# Raspberry_Pi2_Expansion_Slot.net
KiCad netlist of a schematic drawn in Altium Designer
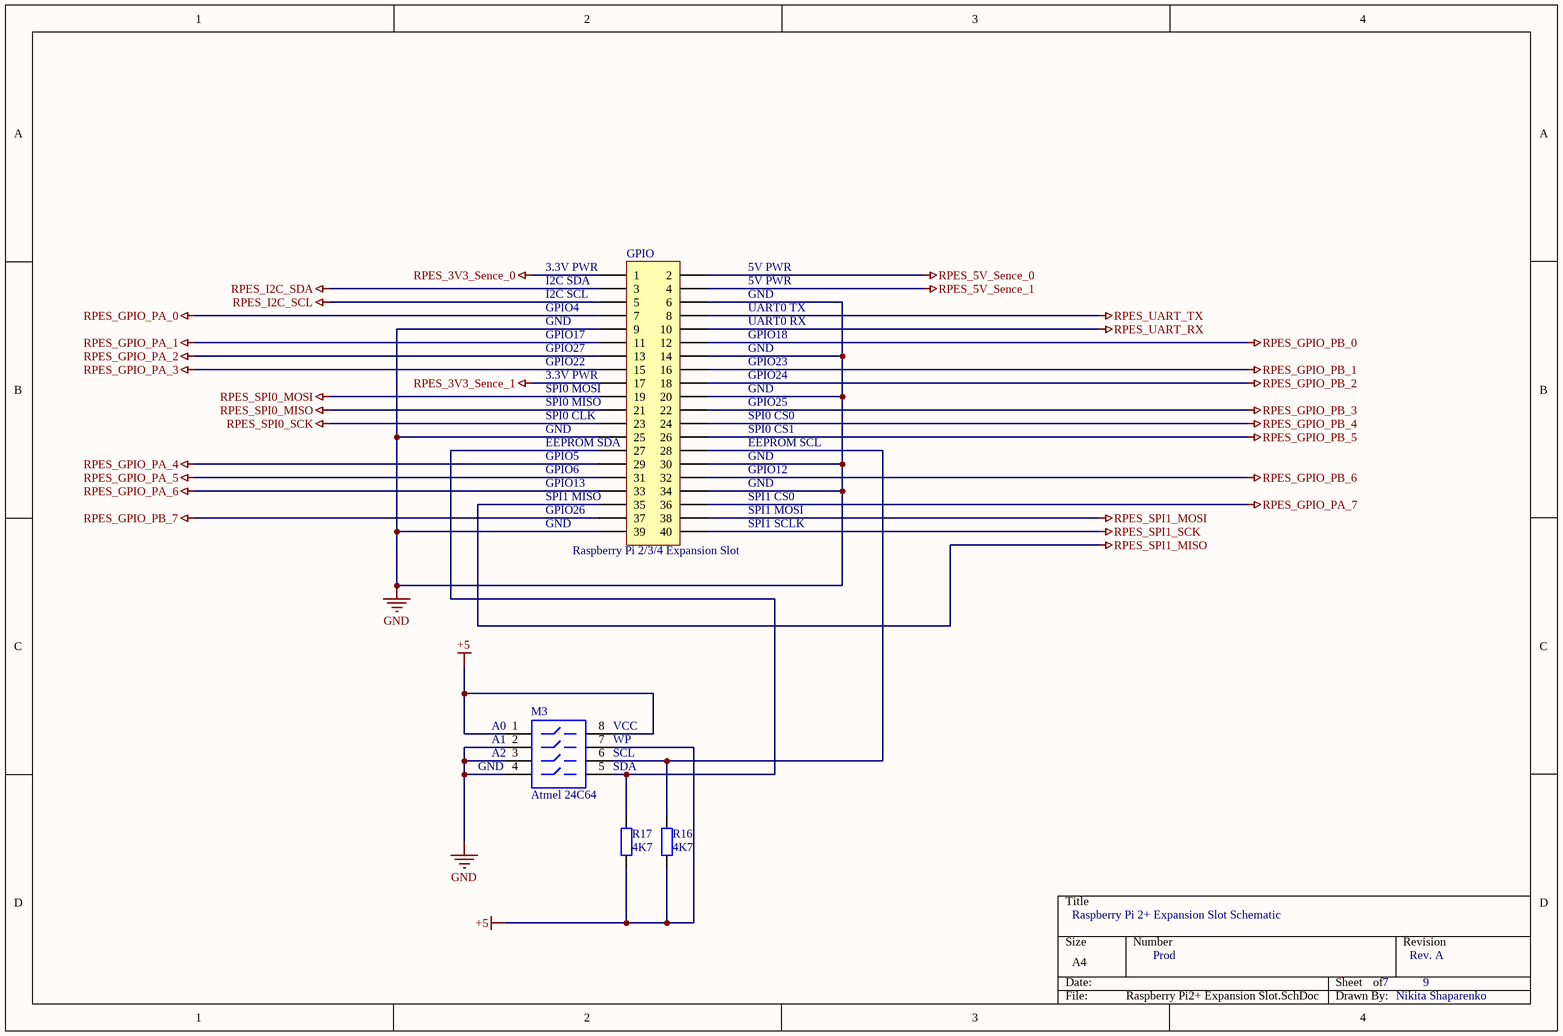
[diagram p0: Raspberry Pi2+ Expansion Slot.SchDoc]

(export (version "E")
  (design (tool "Eeschema 10.0.6"))
  (components
    (comp (ref "GPIO")
      (value "Raspberry Pi 2/3/4 Expansion Slot")
      (footprint "HDR2X20")
      (description "Header, 20-Pin, Dual row")
      (fields (field (name "PUBLISHER") "Altium Limited"))
      (libsource (lib "Miscellaneous Connectors") (part "Header 20X2"))
    )
    (comp (ref "M3")
      (value "Atmel 24C64")
      (footprint "DIP-8")
      (description "DIP Switch")
      (fields (field (name "PUBLISHER") "Altium Limited"))
      (libsource (lib "Miscellaneous Devices") (part "SW-DIP4"))
    )
    (comp (ref "R16")
      (value "4K7")
      (footprint "AXIAL-0.4")
      (description "Resistor")
      (fields (field (name "Comment") "Res2") (field (name "PUBLISHER") "Altium Limited"))
      (libsource (lib "Miscellaneous Devices") (part "Res2"))
    )
    (comp (ref "R17")
      (value "4K7")
      (footprint "AXIAL-0.4")
      (description "Resistor")
      (fields (field (name "Comment") "Res2") (field (name "PUBLISHER") "Altium Limited"))
      (libsource (lib "Miscellaneous Devices") (part "Res2"))
    )
  )
  (nets
    (net (code "1") (name "+5") (class "Default")
      (node (ref "M3") (pin "1") (pinfunction "1_1") (pintype "passive"))
      (node (ref "M3") (pin "7") (pinfunction "7_7") (pintype "passive"))
      (node (ref "M3") (pin "8") (pinfunction "8_8") (pintype "passive"))
      (node (ref "R16") (pin "1") (pinfunction "1_1") (pintype "passive"))
      (node (ref "R17") (pin "1") (pinfunction "1_1") (pintype "passive"))
    )
    (net (code "2") (name "GND") (class "Default")
      (node (ref "GPIO") (pin "14") (pinfunction "14_14") (pintype "passive"))
      (node (ref "GPIO") (pin "20") (pinfunction "20_20") (pintype "passive"))
      (node (ref "GPIO") (pin "25") (pinfunction "25_25") (pintype "passive"))
      (node (ref "GPIO") (pin "30") (pinfunction "30_30") (pintype "passive"))
      (node (ref "GPIO") (pin "34") (pinfunction "34_34") (pintype "passive"))
      (node (ref "GPIO") (pin "39") (pinfunction "39_39") (pintype "passive"))
      (node (ref "GPIO") (pin "6") (pinfunction "6_6") (pintype "passive"))
      (node (ref "GPIO") (pin "9") (pinfunction "9_9") (pintype "passive"))
      (node (ref "M3") (pin "2") (pinfunction "2_2") (pintype "passive"))
      (node (ref "M3") (pin "3") (pinfunction "3_3") (pintype "passive"))
      (node (ref "M3") (pin "4") (pinfunction "4_4") (pintype "passive"))
    )
    (net (code "3") (name "Net-(GPIO-Pad27)") (class "Default")
      (node (ref "GPIO") (pin "27") (pinfunction "27_27") (pintype "passive"))
      (node (ref "M3") (pin "5") (pinfunction "5_5") (pintype "passive"))
      (node (ref "R17") (pin "2") (pinfunction "2_2") (pintype "passive"))
    )
    (net (code "4") (name "Net-(GPIO-Pad28)") (class "Default")
      (node (ref "GPIO") (pin "28") (pinfunction "28_28") (pintype "passive"))
      (node (ref "M3") (pin "6") (pinfunction "6_6") (pintype "passive"))
      (node (ref "R16") (pin "2") (pinfunction "2_2") (pintype "passive"))
    )
    (net (code "5") (name "RPES_3V3_Sence_0") (class "Default")
      (node (ref "GPIO") (pin "1") (pinfunction "1_1") (pintype "passive"))
    )
    (net (code "6") (name "RPES_3V3_Sence_1") (class "Default")
      (node (ref "GPIO") (pin "17") (pinfunction "17_17") (pintype "passive"))
    )
    (net (code "7") (name "RPES_5V_Sence_0") (class "Default")
      (node (ref "GPIO") (pin "2") (pinfunction "2_2") (pintype "passive"))
    )
    (net (code "8") (name "RPES_5V_Sence_1") (class "Default")
      (node (ref "GPIO") (pin "4") (pinfunction "4_4") (pintype "passive"))
    )
    (net (code "9") (name "RPES_GPIO_PA_0") (class "Default")
      (node (ref "GPIO") (pin "7") (pinfunction "7_7") (pintype "passive"))
    )
    (net (code "10") (name "RPES_GPIO_PA_1") (class "Default")
      (node (ref "GPIO") (pin "11") (pinfunction "11_11") (pintype "passive"))
    )
    (net (code "11") (name "RPES_GPIO_PA_2") (class "Default")
      (node (ref "GPIO") (pin "13") (pinfunction "13_13") (pintype "passive"))
    )
    (net (code "12") (name "RPES_GPIO_PA_3") (class "Default")
      (node (ref "GPIO") (pin "15") (pinfunction "15_15") (pintype "passive"))
    )
    (net (code "13") (name "RPES_GPIO_PA_4") (class "Default")
      (node (ref "GPIO") (pin "29") (pinfunction "29_29") (pintype "passive"))
    )
    (net (code "14") (name "RPES_GPIO_PA_5") (class "Default")
      (node (ref "GPIO") (pin "31") (pinfunction "31_31") (pintype "passive"))
    )
    (net (code "15") (name "RPES_GPIO_PA_6") (class "Default")
      (node (ref "GPIO") (pin "33") (pinfunction "33_33") (pintype "passive"))
    )
    (net (code "16") (name "RPES_GPIO_PA_7") (class "Default")
      (node (ref "GPIO") (pin "36") (pinfunction "36_36") (pintype "passive"))
    )
    (net (code "17") (name "RPES_GPIO_PB_0") (class "Default")
      (node (ref "GPIO") (pin "12") (pinfunction "12_12") (pintype "passive"))
    )
    (net (code "18") (name "RPES_GPIO_PB_1") (class "Default")
      (node (ref "GPIO") (pin "16") (pinfunction "16_16") (pintype "passive"))
    )
    (net (code "19") (name "RPES_GPIO_PB_2") (class "Default")
      (node (ref "GPIO") (pin "18") (pinfunction "18_18") (pintype "passive"))
    )
    (net (code "20") (name "RPES_GPIO_PB_3") (class "Default")
      (node (ref "GPIO") (pin "22") (pinfunction "22_22") (pintype "passive"))
    )
    (net (code "21") (name "RPES_GPIO_PB_4") (class "Default")
      (node (ref "GPIO") (pin "24") (pinfunction "24_24") (pintype "passive"))
    )
    (net (code "22") (name "RPES_GPIO_PB_5") (class "Default")
      (node (ref "GPIO") (pin "26") (pinfunction "26_26") (pintype "passive"))
    )
    (net (code "23") (name "RPES_GPIO_PB_6") (class "Default")
      (node (ref "GPIO") (pin "32") (pinfunction "32_32") (pintype "passive"))
    )
    (net (code "24") (name "RPES_GPIO_PB_7") (class "Default")
      (node (ref "GPIO") (pin "37") (pinfunction "37_37") (pintype "passive"))
    )
    (net (code "25") (name "RPES_I2C_SCL") (class "Default")
      (node (ref "GPIO") (pin "5") (pinfunction "5_5") (pintype "passive"))
    )
    (net (code "26") (name "RPES_I2C_SDA") (class "Default")
      (node (ref "GPIO") (pin "3") (pinfunction "3_3") (pintype "passive"))
    )
    (net (code "27") (name "RPES_SPI0_MISO") (class "Default")
      (node (ref "GPIO") (pin "21") (pinfunction "21_21") (pintype "passive"))
    )
    (net (code "28") (name "RPES_SPI0_MOSI") (class "Default")
      (node (ref "GPIO") (pin "19") (pinfunction "19_19") (pintype "passive"))
    )
    (net (code "29") (name "RPES_SPI0_SCK") (class "Default")
      (node (ref "GPIO") (pin "23") (pinfunction "23_23") (pintype "passive"))
    )
    (net (code "30") (name "RPES_SPI1_MISO") (class "Default")
      (node (ref "GPIO") (pin "35") (pinfunction "35_35") (pintype "passive"))
    )
    (net (code "31") (name "RPES_SPI1_MOSI") (class "Default")
      (node (ref "GPIO") (pin "38") (pinfunction "38_38") (pintype "passive"))
    )
    (net (code "32") (name "RPES_SPI1_SCK") (class "Default")
      (node (ref "GPIO") (pin "40") (pinfunction "40_40") (pintype "passive"))
    )
    (net (code "33") (name "RPES_UART_RX") (class "Default")
      (node (ref "GPIO") (pin "10") (pinfunction "10_10") (pintype "passive"))
    )
    (net (code "34") (name "RPES_UART_TX") (class "Default")
      (node (ref "GPIO") (pin "8") (pinfunction "8_8") (pintype "passive"))
    )
  )
)
